# main_indoor_sensor_v0_2.net
KiCad netlist of a schematic drawn in EAGLE
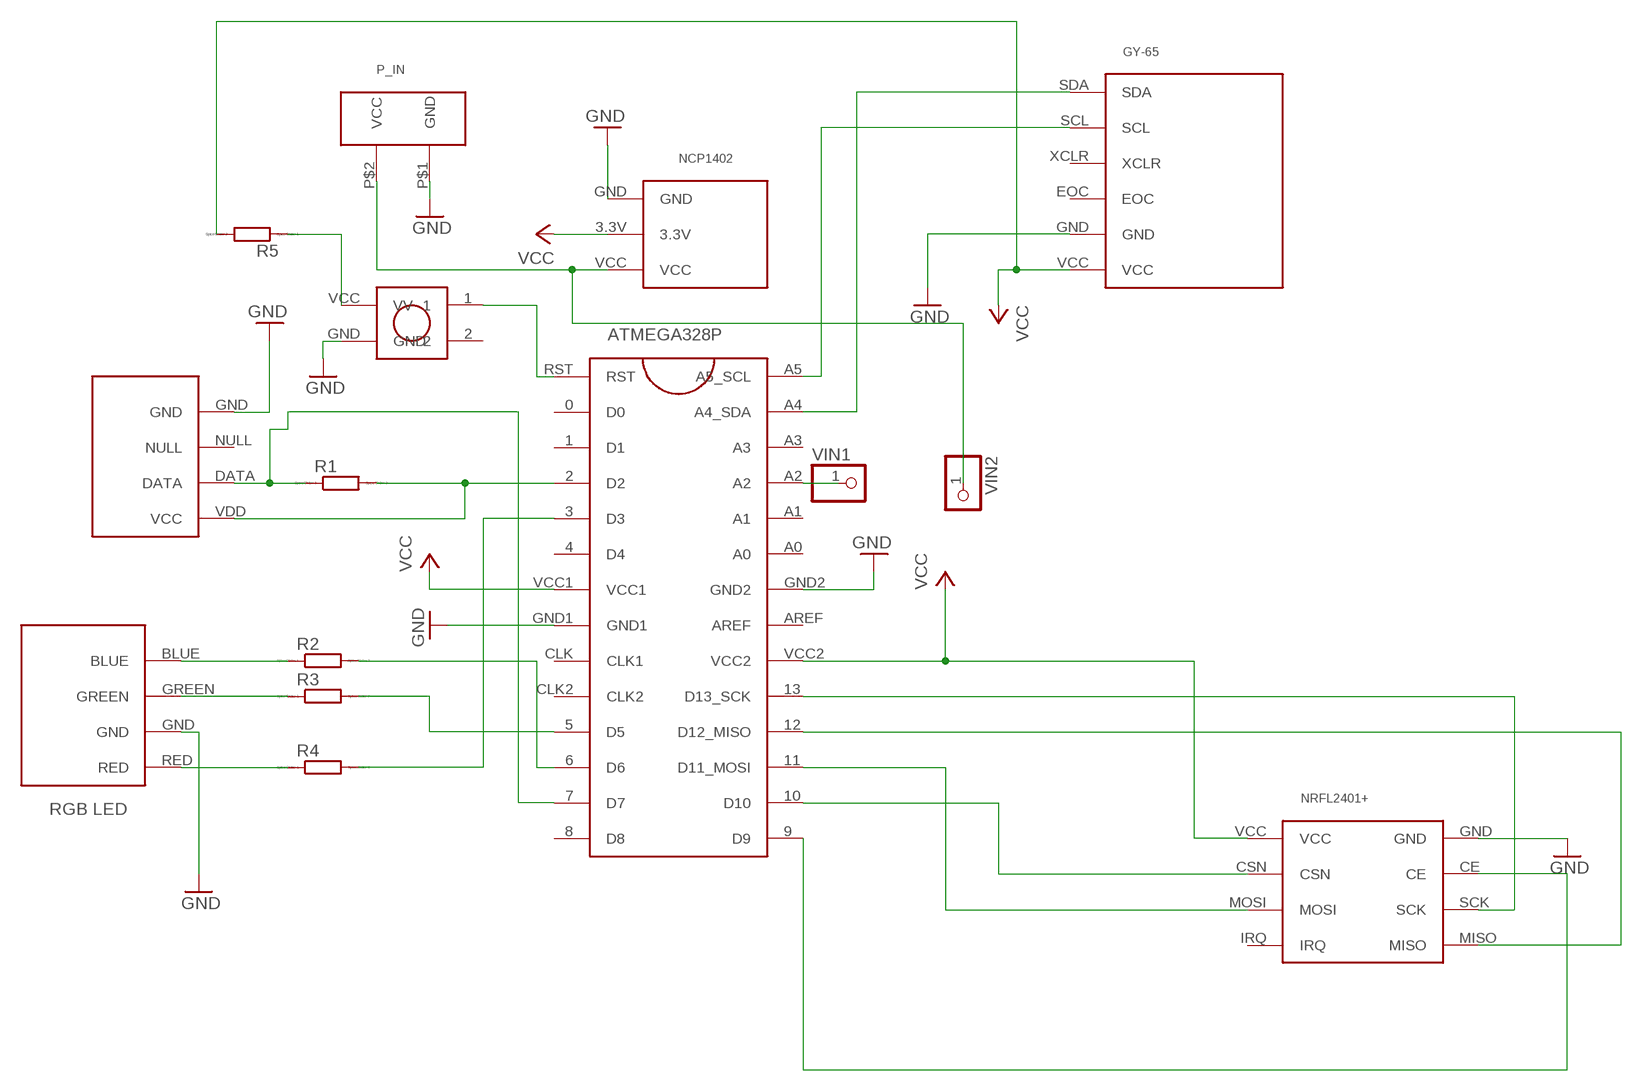
[diagram p0: schematic, sheet 1]

(export (version "E")
  (design (tool "Eeschema 10.0.6"))
  (components
    (comp (ref "GY-65")
      (value "GY-65")
      (footprint "eagle-import:GY_65")
      (libsource (lib "eagle-import") (part "GY-65"))
    )
    (comp (ref "NCP1402")
      (value "NCP1402SPARKFUN")
      (footprint "eagle-import:NCP1402")
      (libsource (lib "eagle-import") (part "NCP1402SPARKFUN"))
    )
    (comp (ref "NRFL2401+")
      (value "NRFL24L01_8P")
      (footprint "eagle-import:NRF24L01_10P")
      (libsource (lib "eagle-import") (part "NRFL24L01_8P"))
    )
    (comp (ref "P_IN")
      (value "2PINCONNECTORSIMPLE")
      (footprint "eagle-import:2PINCONNECTOR")
      (libsource (lib "eagle-import") (part "2PINCONNECTORSIMPLE"))
    )
    (comp (ref "R1")
      (value "R0204/7")
      (footprint "eagle-import:0204_7")
      (libsource (lib "eagle-import") (part "R0204/7"))
    )
    (comp (ref "R2")
      (value "R0204/7")
      (footprint "eagle-import:0204_7")
      (libsource (lib "eagle-import") (part "R0204/7"))
    )
    (comp (ref "R3")
      (value "R0204/7")
      (footprint "eagle-import:0204_7")
      (libsource (lib "eagle-import") (part "R0204/7"))
    )
    (comp (ref "R4")
      (value "R0204/7")
      (footprint "eagle-import:0204_7")
      (libsource (lib "eagle-import") (part "R0204/7"))
    )
    (comp (ref "R5")
      (value "R0204/7")
      (footprint "eagle-import:0204_7")
      (libsource (lib "eagle-import") (part "R0204/7"))
    )
    (comp (ref "U$1")
      (value "ATMEGA328PARDUINO")
      (footprint "eagle-import:ATMEGA328P")
      (libsource (lib "eagle-import") (part "ATMEGA328PARDUINO"))
    )
    (comp (ref "U$2")
      (value "KRS_0612_OK")
      (footprint "eagle-import:KRS0612_RIGHT")
      (libsource (lib "eagle-import") (part "KRS_0612_OK"))
    )
    (comp (ref "U$3")
      (value "DHT22WHITE")
      (footprint "eagle-import:DHT22")
      (libsource (lib "eagle-import") (part "DHT22WHITE"))
    )
    (comp (ref "U$6")
      (value "RGB_LED5MM")
      (footprint "eagle-import:RGB_LED")
      (libsource (lib "eagle-import") (part "RGB_LED5MM"))
    )
    (comp (ref "VIN1")
      (value "PINHD-1X1")
      (footprint "eagle-import:1X01")
      (libsource (lib "eagle-import") (part "PINHD-1X1"))
    )
    (comp (ref "VIN2")
      (value "PINHD-1X1")
      (footprint "eagle-import:1X01")
      (libsource (lib "eagle-import") (part "PINHD-1X1"))
    )
  )
  (nets
    (net (code "1") (name "GND") (class "Default")
      (node (ref "GY-65") (pin "GND") (pinfunction "GND_GND") (pintype "bidirectional"))
      (node (ref "NCP1402") (pin "GND") (pinfunction "GND_GND") (pintype "bidirectional"))
      (node (ref "NRFL2401+") (pin "GND") (pinfunction "GND_GND") (pintype "bidirectional"))
      (node (ref "P_IN") (pin "P$1") (pinfunction "GND_P$1") (pintype "bidirectional"))
      (node (ref "U$1") (pin "GND1") (pinfunction "GND1_GND1") (pintype "bidirectional"))
      (node (ref "U$1") (pin "GND2") (pinfunction "GND2_GND2") (pintype "bidirectional"))
      (node (ref "U$2") (pin "GND") (pinfunction "GND_GND") (pintype "bidirectional"))
      (node (ref "U$3") (pin "GND") (pinfunction "GND_GND") (pintype "bidirectional"))
      (node (ref "U$6") (pin "GND") (pinfunction "GND_GND") (pintype "bidirectional"))
    )
    (net (code "2") (name "Net-(P_IN-VCC)") (class "Default")
      (node (ref "NCP1402") (pin "VCC") (pinfunction "VCC_VCC") (pintype "bidirectional"))
      (node (ref "P_IN") (pin "P$2") (pinfunction "VCC_P$2") (pintype "bidirectional"))
      (node (ref "VIN2") (pin "1") (pinfunction "1_1") (pintype "passive"))
    )
    (net (code "3") (name "Net-(R2-Pad1)") (class "Default")
      (node (ref "R2") (pin "1") (pinfunction "1_1") (pintype "passive"))
      (node (ref "U$6") (pin "BLUE") (pinfunction "BLUE_BLUE") (pintype "bidirectional"))
    )
    (net (code "4") (name "Net-(R3-Pad1)") (class "Default")
      (node (ref "R3") (pin "1") (pinfunction "1_1") (pintype "passive"))
      (node (ref "U$6") (pin "GREEN") (pinfunction "GREEN_GREEN") (pintype "bidirectional"))
    )
    (net (code "5") (name "Net-(R4-Pad1)") (class "Default")
      (node (ref "R4") (pin "1") (pinfunction "1_1") (pintype "passive"))
      (node (ref "U$6") (pin "RED") (pinfunction "RED_RED") (pintype "bidirectional"))
    )
    (net (code "6") (name "Net-(U$1-A4_SDA)") (class "Default")
      (node (ref "GY-65") (pin "SDA") (pinfunction "SDA_SDA") (pintype "bidirectional"))
      (node (ref "U$1") (pin "A4") (pinfunction "A4_SDA_A4") (pintype "bidirectional"))
    )
    (net (code "7") (name "Net-(U$1-A5_SCL)") (class "Default")
      (node (ref "GY-65") (pin "SCL") (pinfunction "SCL_SCL") (pintype "bidirectional"))
      (node (ref "U$1") (pin "A5") (pinfunction "A5_SCL_A5") (pintype "bidirectional"))
    )
    (net (code "8") (name "Net-(U$1-D2)") (class "Default")
      (node (ref "R1") (pin "2") (pinfunction "2_2") (pintype "passive"))
      (node (ref "U$1") (pin "2") (pinfunction "D2_2") (pintype "bidirectional"))
      (node (ref "U$3") (pin "VDD") (pinfunction "VCC_VDD") (pintype "bidirectional"))
    )
    (net (code "9") (name "Net-(U$1-D3)") (class "Default")
      (node (ref "R4") (pin "2") (pinfunction "2_2") (pintype "passive"))
      (node (ref "U$1") (pin "3") (pinfunction "D3_3") (pintype "bidirectional"))
    )
    (net (code "10") (name "Net-(U$1-D5)") (class "Default")
      (node (ref "R3") (pin "2") (pinfunction "2_2") (pintype "passive"))
      (node (ref "U$1") (pin "5") (pinfunction "D5_5") (pintype "bidirectional"))
    )
    (net (code "11") (name "Net-(U$1-D6)") (class "Default")
      (node (ref "R2") (pin "2") (pinfunction "2_2") (pintype "passive"))
      (node (ref "U$1") (pin "6") (pinfunction "D6_6") (pintype "bidirectional"))
    )
    (net (code "12") (name "Net-(U$1-D7)") (class "Default")
      (node (ref "R1") (pin "1") (pinfunction "1_1") (pintype "passive"))
      (node (ref "U$1") (pin "7") (pinfunction "D7_7") (pintype "bidirectional"))
      (node (ref "U$3") (pin "DATA") (pinfunction "DATA_DATA") (pintype "bidirectional"))
    )
    (net (code "13") (name "Net-(U$1-D9)") (class "Default")
      (node (ref "NRFL2401+") (pin "CE") (pinfunction "CE_CE") (pintype "bidirectional"))
      (node (ref "U$1") (pin "9") (pinfunction "D9_9") (pintype "bidirectional"))
    )
    (net (code "14") (name "Net-(U$1-D10)") (class "Default")
      (node (ref "NRFL2401+") (pin "CSN") (pinfunction "CSN_CSN") (pintype "bidirectional"))
      (node (ref "U$1") (pin "10") (pinfunction "D10_10") (pintype "bidirectional"))
    )
    (net (code "15") (name "Net-(U$1-D11_MOSI)") (class "Default")
      (node (ref "NRFL2401+") (pin "MOSI") (pinfunction "MOSI_MOSI") (pintype "bidirectional"))
      (node (ref "U$1") (pin "11") (pinfunction "D11_MOSI_11") (pintype "bidirectional"))
    )
    (net (code "16") (name "Net-(U$1-D12_MISO)") (class "Default")
      (node (ref "NRFL2401+") (pin "MISO") (pinfunction "MISO_MISO") (pintype "bidirectional"))
      (node (ref "U$1") (pin "12") (pinfunction "D12_MISO_12") (pintype "bidirectional"))
    )
    (net (code "17") (name "Net-(U$1-D13_SCK)") (class "Default")
      (node (ref "NRFL2401+") (pin "SCK") (pinfunction "SCK_SCK") (pintype "bidirectional"))
      (node (ref "U$1") (pin "13") (pinfunction "D13_SCK_13") (pintype "bidirectional"))
    )
    (net (code "18") (name "Net-(U$1-PadA2)") (class "Default")
      (node (ref "U$1") (pin "A2") (pinfunction "A2_A2") (pintype "bidirectional"))
      (node (ref "VIN1") (pin "1") (pinfunction "1_1") (pintype "passive"))
    )
    (net (code "19") (name "Net-(U$1-PadRST)") (class "Default")
      (node (ref "U$1") (pin "RST") (pinfunction "RST_RST") (pintype "bidirectional"))
      (node (ref "U$2") (pin "1") (pinfunction "1_1") (pintype "bidirectional"))
    )
    (net (code "20") (name "Net-(U$2-VV)") (class "Default")
      (node (ref "R5") (pin "1") (pinfunction "1_1") (pintype "passive"))
      (node (ref "U$2") (pin "VCC") (pinfunction "VV_VCC") (pintype "bidirectional"))
    )
    (net (code "21") (name "VCC") (class "Default")
      (node (ref "GY-65") (pin "VCC") (pinfunction "VCC_VCC") (pintype "bidirectional"))
      (node (ref "NCP1402") (pin "3.3V") (pinfunction "3.3V_3.3V") (pintype "bidirectional"))
      (node (ref "NRFL2401+") (pin "VCC") (pinfunction "VCC_VCC") (pintype "bidirectional"))
      (node (ref "R5") (pin "2") (pinfunction "2_2") (pintype "passive"))
      (node (ref "U$1") (pin "VCC1") (pinfunction "VCC1_VCC1") (pintype "bidirectional"))
      (node (ref "U$1") (pin "VCC2") (pinfunction "VCC2_VCC2") (pintype "bidirectional"))
    )
    (net (code "22") (name "unconnected-(GY-65-PadEOC)") (class "Default")
      (node (ref "GY-65") (pin "EOC") (pinfunction "EOC_EOC") (pintype "bidirectional"))
    )
    (net (code "23") (name "unconnected-(GY-65-PadXCLR)") (class "Default")
      (node (ref "GY-65") (pin "XCLR") (pinfunction "XCLR_XCLR") (pintype "bidirectional"))
    )
    (net (code "24") (name "unconnected-(NRFL2401+-PadIRQ)") (class "Default")
      (node (ref "NRFL2401+") (pin "IRQ") (pinfunction "IRQ_IRQ") (pintype "bidirectional"))
    )
    (net (code "25") (name "unconnected-(U$1-CLK1-PadCLK)") (class "Default")
      (node (ref "U$1") (pin "CLK") (pinfunction "CLK1_CLK") (pintype "bidirectional"))
    )
    (net (code "26") (name "unconnected-(U$1-D0-Pad0)") (class "Default")
      (node (ref "U$1") (pin "0") (pinfunction "D0_0") (pintype "bidirectional"))
    )
    (net (code "27") (name "unconnected-(U$1-D1-Pad1)") (class "Default")
      (node (ref "U$1") (pin "1") (pinfunction "D1_1") (pintype "bidirectional"))
    )
    (net (code "28") (name "unconnected-(U$1-D4-Pad4)") (class "Default")
      (node (ref "U$1") (pin "4") (pinfunction "D4_4") (pintype "bidirectional"))
    )
    (net (code "29") (name "unconnected-(U$1-D8-Pad8)") (class "Default")
      (node (ref "U$1") (pin "8") (pinfunction "D8_8") (pintype "bidirectional"))
    )
    (net (code "30") (name "unconnected-(U$1-PadA0)") (class "Default")
      (node (ref "U$1") (pin "A0") (pinfunction "A0_A0") (pintype "bidirectional"))
    )
    (net (code "31") (name "unconnected-(U$1-PadA1)") (class "Default")
      (node (ref "U$1") (pin "A1") (pinfunction "A1_A1") (pintype "bidirectional"))
    )
    (net (code "32") (name "unconnected-(U$1-PadA3)") (class "Default")
      (node (ref "U$1") (pin "A3") (pinfunction "A3_A3") (pintype "bidirectional"))
    )
    (net (code "33") (name "unconnected-(U$1-PadAREF)") (class "Default")
      (node (ref "U$1") (pin "AREF") (pinfunction "AREF_AREF") (pintype "bidirectional"))
    )
    (net (code "34") (name "unconnected-(U$1-PadCLK2)") (class "Default")
      (node (ref "U$1") (pin "CLK2") (pinfunction "CLK2_CLK2") (pintype "bidirectional"))
    )
    (net (code "35") (name "unconnected-(U$2-Pad2)") (class "Default")
      (node (ref "U$2") (pin "2") (pinfunction "2_2") (pintype "bidirectional"))
    )
    (net (code "36") (name "unconnected-(U$3-PadNULL)") (class "Default")
      (node (ref "U$3") (pin "NULL") (pinfunction "NULL_NULL") (pintype "bidirectional"))
    )
  )
)
